# Mech_Interface_Starboard.net
KiCad netlist of a schematic drawn in Altium Designer
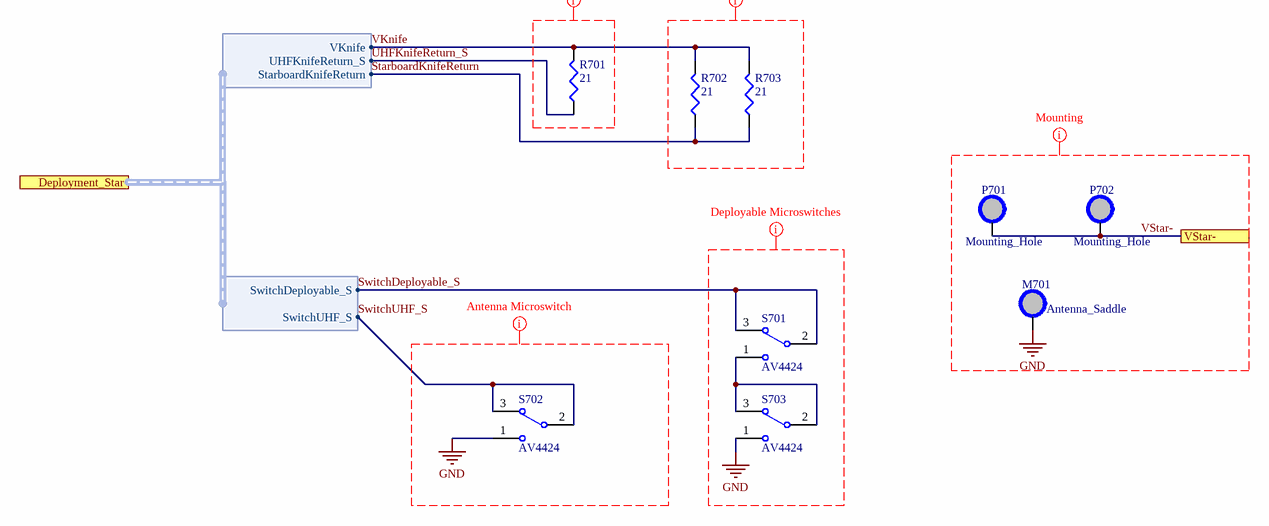
[diagram p0: Mech_Interface_Starboard.SchDoc]

(export (version "E")
  (design (tool "Eeschema 10.0.6"))
  (components
    (comp (ref "M701")
      (value "Antenna_Saddle")
      (footprint "ANTENNA_SADDLE")
      (fields
        (field (name "PART NUMBER") "PXX-ABS-00001")
        (field (name "MANUFACTURER PART NUMBER") "Custom")
        (field (name "PUBLISHER") "AlbertaSat")
      )
      (libsource (lib "Database") (part "Mounting_Hole"))
    )
    (comp (ref "P701")
      (value "Mounting_Hole")
      (footprint "DEPHINGE_MOUNTING_HOLE_BODY")
      (fields
        (field (name "PART NUMBER") "PXX-ABS-00004")
        (field (name "MANUFACTURER PART NUMBER") "Custom")
        (field (name "PUBLISHER") "AlbertaSat")
      )
      (libsource (lib "Database") (part "Mounting_Hole"))
    )
    (comp (ref "P702")
      (value "Mounting_Hole")
      (footprint "DEPHINGE_MOUNTING_HOLE_BODY")
      (fields
        (field (name "PART NUMBER") "PXX-ABS-00004")
        (field (name "MANUFACTURER PART NUMBER") "Custom")
        (field (name "PUBLISHER") "AlbertaSat")
      )
      (libsource (lib "Database") (part "Mounting_Hole"))
    )
    (comp (ref "R701")
      (value "21")
      (footprint "VSH-CPF1")
      (description "21 Ohms ±1% 1W Through Hole Resistor Axial Flame Proof, Moisture Resistant, Safety Metal Film")
      (fields
        (field (name "PART NUMBER") "PR-VSH-00317")
        (field (name "MANUFACTURER PART NUMBER") "CPF121R000FKEE6")
        (field (name "PUBLISHER") "AlbertaSat")
      )
      (libsource (lib "Database") (part "Res3"))
    )
    (comp (ref "R702")
      (value "21")
      (footprint "VSH-CPF1")
      (description "21 Ohms ±1% 1W Through Hole Resistor Axial Flame Proof, Moisture Resistant, Safety Metal Film")
      (fields
        (field (name "PART NUMBER") "PR-VSH-00317")
        (field (name "MANUFACTURER PART NUMBER") "CPF121R000FKEE6")
        (field (name "PUBLISHER") "AlbertaSat")
      )
      (libsource (lib "Database") (part "Res3"))
    )
    (comp (ref "R703")
      (value "21")
      (footprint "VSH-CPF1")
      (description "21 Ohms ±1% 1W Through Hole Resistor Axial Flame Proof, Moisture Resistant, Safety Metal Film")
      (fields
        (field (name "PART NUMBER") "PR-VSH-00317")
        (field (name "MANUFACTURER PART NUMBER") "CPF121R000FKEE6")
        (field (name "PUBLISHER") "AlbertaSat")
      )
      (libsource (lib "Database") (part "Res3"))
    )
    (comp (ref "S701")
      (value "AV4424")
      (footprint "PANA-AV4424")
      (description "SWITCH SNAP ACT SPDT 500MA 30V")
      (fields (field (name "PART NUMBER") "20035"))
      (libsource (lib "Database") (part "SW-SPDT"))
    )
    (comp (ref "S702")
      (value "AV4424")
      (footprint "PANA-AV4424")
      (description "SWITCH SNAP ACT SPDT 500MA 30V")
      (fields (field (name "PART NUMBER") "20035"))
      (libsource (lib "Database") (part "SW-SPDT"))
    )
    (comp (ref "S703")
      (value "AV4424")
      (footprint "PANA-AV4424")
      (description "SWITCH SNAP ACT SPDT 500MA 30V")
      (fields (field (name "PART NUMBER") "20035"))
      (libsource (lib "Database") (part "SW-SPDT"))
    )
  )
  (nets
    (net (code "2") (name "/StarboardKnifeReturn") (class "Default")
      (node (ref "R702") (pin "1") (pinfunction "1_1") (pintype "passive"))
      (node (ref "R703") (pin "1") (pinfunction "1_1") (pintype "passive"))
    )
    (net (code "3") (name "/SwitchDeployable_S") (class "Default")
      (node (ref "S701") (pin "2") (pinfunction "COM_2") (pintype "passive"))
      (node (ref "S701") (pin "3") (pinfunction "NC_3") (pintype "passive"))
    )
    (net (code "4") (name "/SwitchUHF_S") (class "Default")
      (node (ref "S702") (pin "2") (pinfunction "COM_2") (pintype "passive"))
      (node (ref "S702") (pin "3") (pinfunction "NC_3") (pintype "passive"))
    )
    (net (code "5") (name "/UHFKnifeReturn_S") (class "Default")
      (node (ref "R701") (pin "1") (pinfunction "1_1") (pintype "passive"))
    )
    (net (code "6") (name "/VKnife") (class "Default")
      (node (ref "R701") (pin "2") (pinfunction "2_2") (pintype "passive"))
      (node (ref "R702") (pin "2") (pinfunction "2_2") (pintype "passive"))
      (node (ref "R703") (pin "2") (pinfunction "2_2") (pintype "passive"))
    )
    (net (code "7") (name "/VStar-") (class "Default")
      (node (ref "P701") (pin "1") (pinfunction "0_1") (pintype "passive"))
      (node (ref "P702") (pin "1") (pinfunction "0_1") (pintype "passive"))
    )
    (net (code "9") (name "GND") (class "Default")
      (node (ref "M701") (pin "1") (pinfunction "0_1") (pintype "passive"))
      (node (ref "S702") (pin "1") (pinfunction "NO_1") (pintype "passive"))
      (node (ref "S703") (pin "1") (pinfunction "NO_1") (pintype "passive"))
    )
    (net (code "10") (name "Net-(S701-NO)") (class "Default")
      (node (ref "S701") (pin "1") (pinfunction "NO_1") (pintype "passive"))
      (node (ref "S703") (pin "2") (pinfunction "COM_2") (pintype "passive"))
      (node (ref "S703") (pin "3") (pinfunction "NC_3") (pintype "passive"))
    )
  )
)
